# 3_TopLevel.net
KiCad netlist of a schematic drawn in Altium Designer
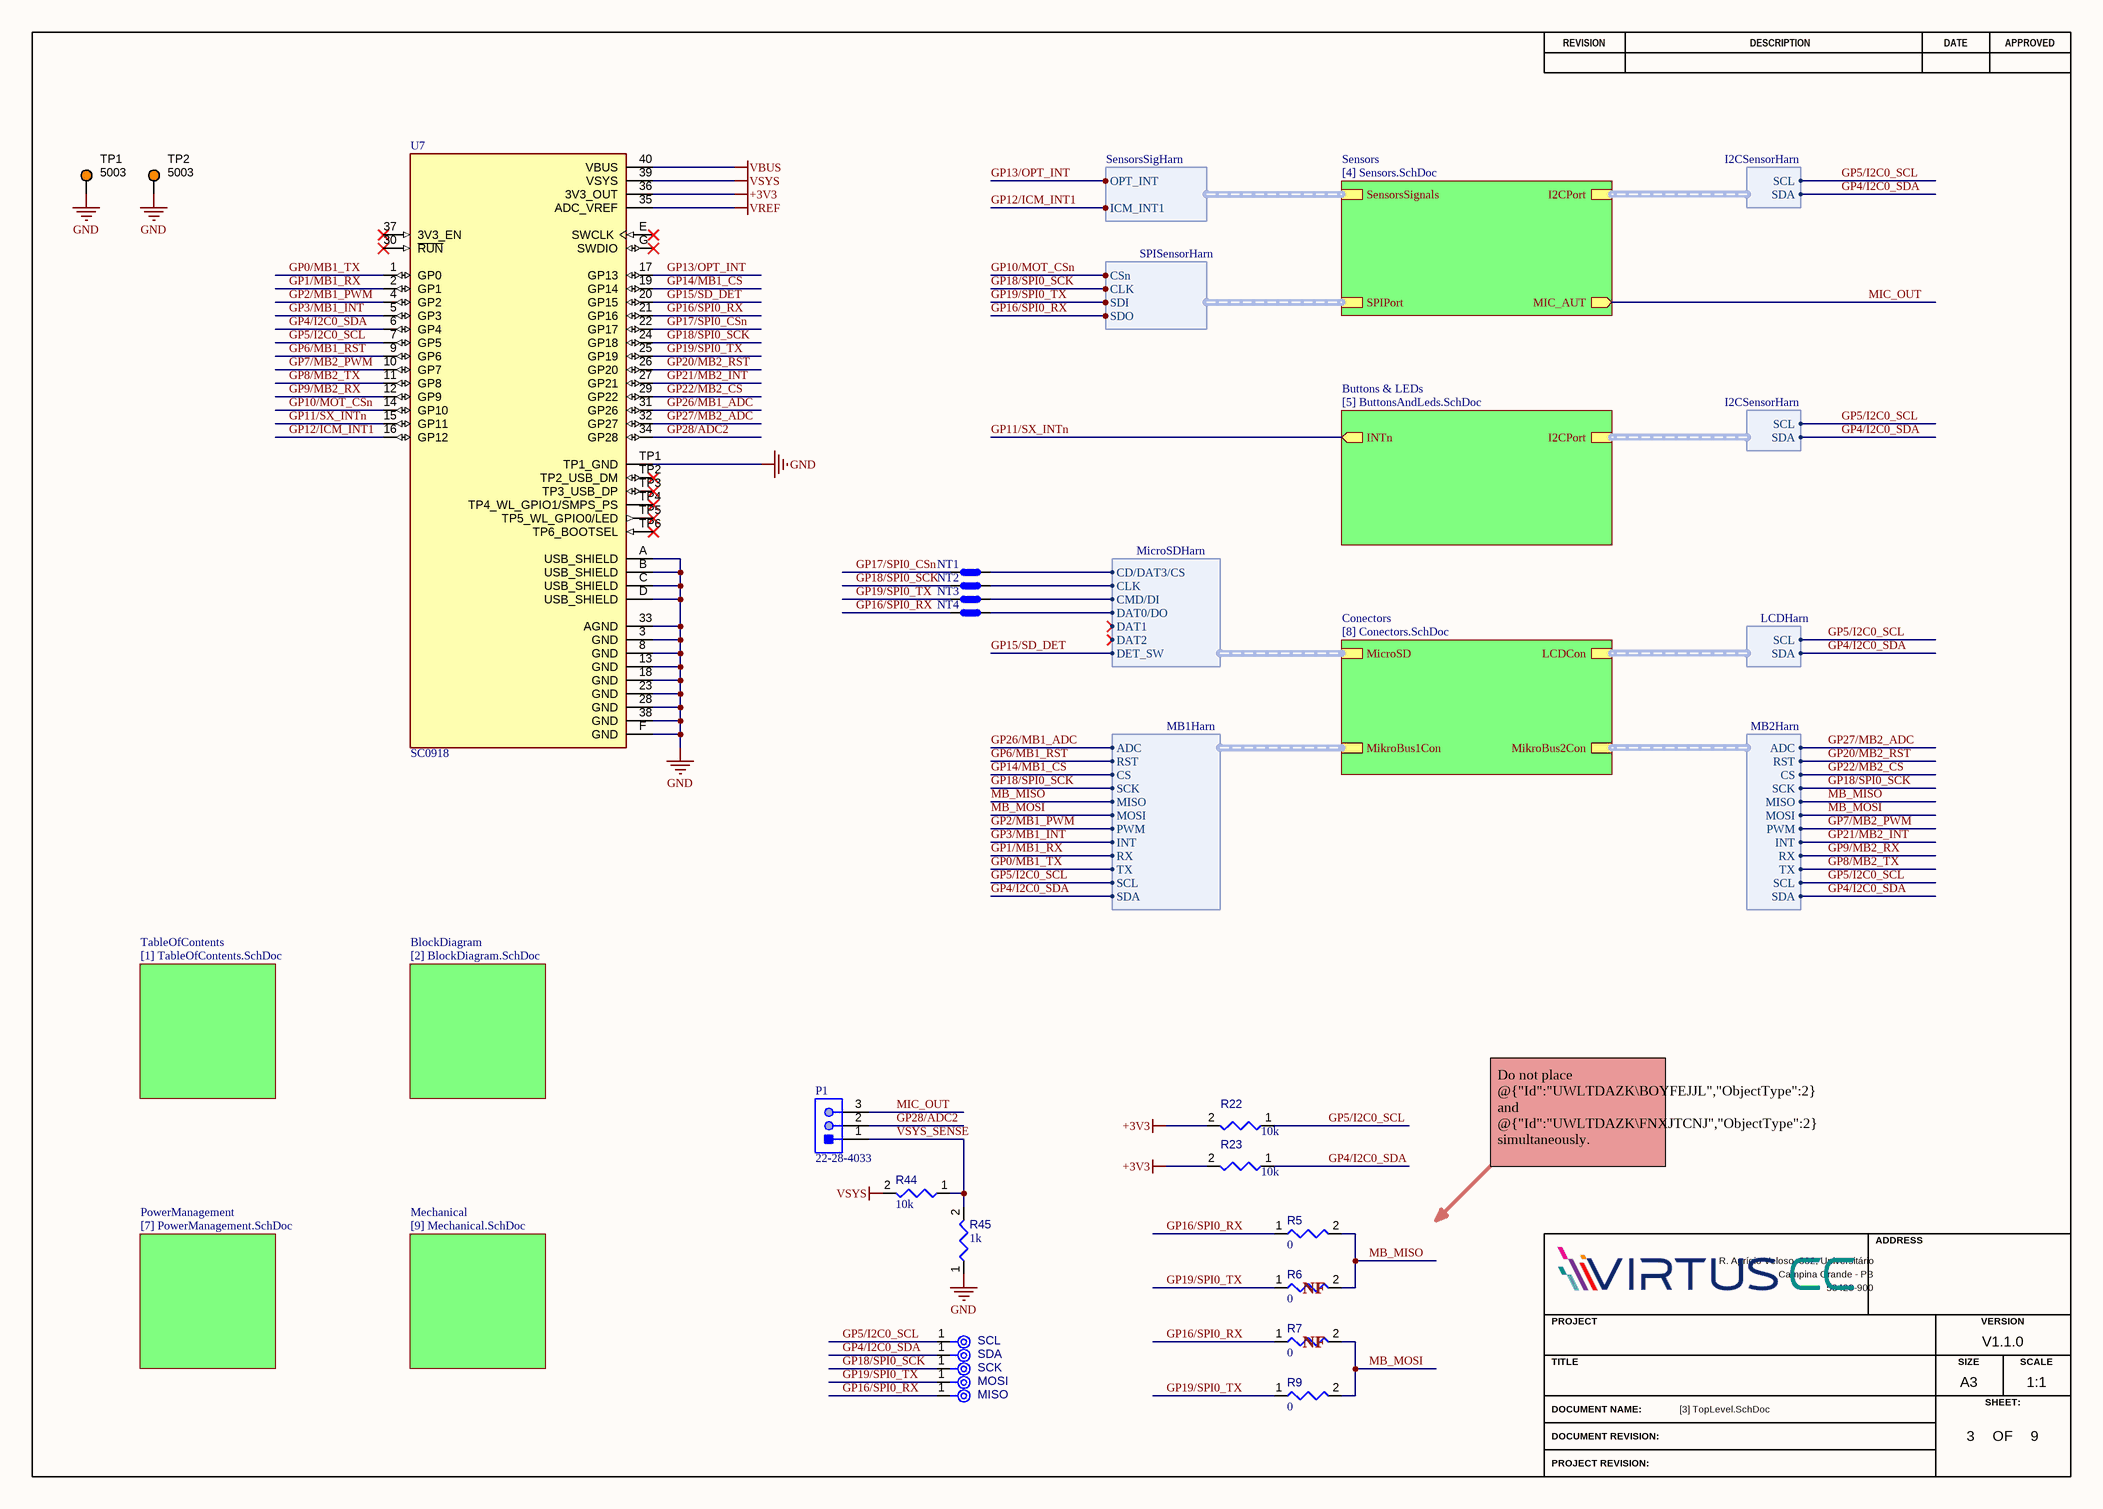
[diagram p0: [3] TopLevel.SchDoc]

(export (version "E")
  (design (tool "Eeschema 10.0.6"))
  (components
    (comp (ref "MISO")
      (value "TPAD6R")
      (footprint "TP06R")
      (description "0.6mm round")
      (libsource (lib "UFCG - Universidade Federal de Campina Grande") (part "CMP-001-0001-4"))
    )
    (comp (ref "MOSI")
      (value "TPAD6R")
      (footprint "TP06R")
      (description "0.6mm round")
      (libsource (lib "UFCG - Universidade Federal de Campina Grande") (part "CMP-001-0001-4"))
    )
    (comp (ref "NT1")
      (value "Net Tie")
      (footprint "New footprint 1")
      (description "Net Tie 0.3mm")
      (libsource (lib "UFCG - Universidade Federal de Campina Grande") (part "NetTie"))
    )
    (comp (ref "NT2")
      (value "Net Tie")
      (footprint "New footprint 1")
      (description "Net Tie 0.3mm")
      (libsource (lib "UFCG - Universidade Federal de Campina Grande") (part "NetTie"))
    )
    (comp (ref "NT3")
      (value "Net Tie")
      (footprint "New footprint 1")
      (description "Net Tie 0.3mm")
      (libsource (lib "UFCG - Universidade Federal de Campina Grande") (part "NetTie"))
    )
    (comp (ref "NT4")
      (value "Net Tie")
      (footprint "New footprint 1")
      (description "Net Tie 0.3mm")
      (libsource (lib "UFCG - Universidade Federal de Campina Grande") (part "NetTie"))
    )
    (comp (ref "P1")
      (value "22-28-4033")
      (footprint "MOLX-22-28-4033_V")
      (description "KK 254 Breakaway Header Vertical 3 Circuits 0.38um Gold Selective Plating Mating Pin 6.09mm")
      (libsource (lib "UFCG - Universidade Federal de Campina Grande") (part "CN-1P-M-R3"))
    )
    (comp (ref "R5")
      (value "0")
      (footprint "RESC0603(1608)_L")
      (description "Chip Resistor, 0 Ohm, 0.1 W, -55 to 155 degC, 0603 (1608 Metric)")
      (fields (field (name "TOLERANCE") "5%") (field (name "POWER") "100mW"))
      (libsource (lib "UFCG - Universidade Federal de Campina Grande") (part "RES-2"))
    )
    (comp (ref "R6")
      (value "0")
      (footprint "RESC0603(1608)_L")
      (description "Chip Resistor, 0 Ohm, 0.1 W, -55 to 155 degC, 0603 (1608 Metric)")
      (fields (field (name "TOLERANCE") "5%") (field (name "POWER") "100mW"))
      (libsource (lib "UFCG - Universidade Federal de Campina Grande") (part "RES-2"))
    )
    (comp (ref "R7")
      (value "0")
      (footprint "RESC0603(1608)_L")
      (description "Chip Resistor, 0 Ohm, 0.1 W, -55 to 155 degC, 0603 (1608 Metric)")
      (fields (field (name "TOLERANCE") "5%") (field (name "POWER") "100mW"))
      (libsource (lib "UFCG - Universidade Federal de Campina Grande") (part "RES-2"))
    )
    (comp (ref "R9")
      (value "0")
      (footprint "RESC0603(1608)_L")
      (description "Chip Resistor, 0 Ohm, 0.1 W, -55 to 155 degC, 0603 (1608 Metric)")
      (fields (field (name "TOLERANCE") "5%") (field (name "POWER") "100mW"))
      (libsource (lib "UFCG - Universidade Federal de Campina Grande") (part "RES-2"))
    )
    (comp (ref "R22")
      (value "10k")
      (footprint "RESC0603(1608)_L")
      (description "Chip Resistor, 10 KOhm, +/- 1%, 01 W, -55 to 155 degC, 0603 (1608 Metric)")
      (fields (field (name "POWER") "100mW") (field (name "TOLERANCE") "1%"))
      (libsource (lib "UFCG - Universidade Federal de Campina Grande") (part "RES-2"))
    )
    (comp (ref "R23")
      (value "10k")
      (footprint "RESC0603(1608)_L")
      (description "Chip Resistor, 10 KOhm, +/- 1%, 01 W, -55 to 155 degC, 0603 (1608 Metric)")
      (fields (field (name "POWER") "100mW") (field (name "TOLERANCE") "1%"))
      (libsource (lib "UFCG - Universidade Federal de Campina Grande") (part "RES-2"))
    )
    (comp (ref "R44")
      (value "10k")
      (footprint "RESC0603(1608)_L")
      (description "Chip Resistor, 10 KOhm, +/- 1%, 01 W, -55 to 155 degC, 0603 (1608 Metric)")
      (fields (field (name "POWER") "100mW") (field (name "TOLERANCE") "1%"))
      (libsource (lib "UFCG - Universidade Federal de Campina Grande") (part "RES-2"))
    )
    (comp (ref "R45")
      (value "1k")
      (footprint "RESC0603(1608)_L")
      (description "Chip Resistor, 1 KOhm, +/-1%, 0.1 W, -55 to 155 degC, 0603 (1608 Metric)")
      (fields (field (name "POWER") "100mW") (field (name "TOLERANCE") "1%"))
      (libsource (lib "UFCG - Universidade Federal de Campina Grande") (part "RES-2"))
    )
    (comp (ref "SCK")
      (value "TPAD6R")
      (footprint "TP06R")
      (description "0.6mm round")
      (libsource (lib "UFCG - Universidade Federal de Campina Grande") (part "CMP-001-0001-4"))
    )
    (comp (ref "SCL")
      (value "TPAD6R")
      (footprint "TP06R")
      (description "0.6mm round")
      (libsource (lib "UFCG - Universidade Federal de Campina Grande") (part "CMP-001-0001-4"))
    )
    (comp (ref "SDA")
      (value "TPAD6R")
      (footprint "TP06R")
      (description "0.6mm round")
      (libsource (lib "UFCG - Universidade Federal de Campina Grande") (part "CMP-001-0001-4"))
    )
    (comp (ref "TP1")
      (value "5003")
      (footprint "KSTN-5003")
      (description "Test Point, Orange, Height 4.6 mm, Tail Length 3 mm, 1-Pin THD, RoHS")
      (fields (field (name "MANUFACTURER") "Keystone"))
      (libsource (lib "UFCG - Universidade Federal de Campina Grande") (part "TESTPOINT_ORANGE"))
    )
    (comp (ref "TP2")
      (value "5003")
      (footprint "KSTN-5003")
      (description "Test Point, Orange, Height 4.6 mm, Tail Length 3 mm, 1-Pin THD, RoHS")
      (fields (field (name "MANUFACTURER") "Keystone"))
      (libsource (lib "UFCG - Universidade Federal de Campina Grande") (part "TESTPOINT_ORANGE"))
    )
    (comp (ref "U7")
      (value "SC0918")
      (footprint "MODULE_SC0918")
      (description "Raspberry Pi Pico W RP2040")
      (fields (field (name "MF") "Raspberry Pi"))
      (libsource (lib "UFCG - Universidade Federal de Campina Grande") (part "SC0918"))
    )
  )
  (nets
    (net (code "8") (name "+3V3") (class "Default")
      (node (ref "R22") (pin "2") (pinfunction "2_2") (pintype "passive"))
      (node (ref "R23") (pin "2") (pinfunction "2_2") (pintype "passive"))
      (node (ref "U7") (pin "36") (pinfunction "3V3_OUT_36") (pintype "power_in"))
    )
    (net (code "9") (name "/CD{slash}DAT3{slash}CS") (class "Default")
      (node (ref "NT1") (pin "2") (pintype "passive"))
    )
    (net (code "10") (name "/CMD{slash}DI") (class "Default")
      (node (ref "NT3") (pin "2") (pintype "passive"))
    )
    (net (code "11") (name "/DAT0{slash}DO") (class "Default")
      (node (ref "NT4") (pin "2") (pintype "passive"))
    )
    (net (code "12") (name "/GP0{slash}MB1_TX") (class "Default")
      (node (ref "U7") (pin "1") (pinfunction "GP0_1") (pintype "bidirectional"))
    )
    (net (code "13") (name "/GP1{slash}MB1_RX") (class "Default")
      (node (ref "U7") (pin "2") (pinfunction "GP1_2") (pintype "bidirectional"))
    )
    (net (code "14") (name "/GP2{slash}MB1_PWM") (class "Default")
      (node (ref "U7") (pin "4") (pinfunction "GP2_4") (pintype "bidirectional"))
    )
    (net (code "15") (name "/GP3{slash}MB1_INT") (class "Default")
      (node (ref "U7") (pin "5") (pinfunction "GP3_5") (pintype "bidirectional"))
    )
    (net (code "16") (name "/GP4{slash}I2C0_SDA") (class "Default")
      (node (ref "R23") (pin "1") (pinfunction "1_1") (pintype "passive"))
      (node (ref "SDA") (pin "1") (pinfunction "TP_1") (pintype "passive"))
      (node (ref "U7") (pin "6") (pinfunction "GP4_6") (pintype "bidirectional"))
    )
    (net (code "17") (name "/GP5{slash}I2C0_SCL") (class "Default")
      (node (ref "R22") (pin "1") (pinfunction "1_1") (pintype "passive"))
      (node (ref "SCL") (pin "1") (pinfunction "TP_1") (pintype "passive"))
      (node (ref "U7") (pin "7") (pinfunction "GP5_7") (pintype "bidirectional"))
    )
    (net (code "18") (name "/GP6{slash}MB1_RST") (class "Default")
      (node (ref "U7") (pin "9") (pinfunction "GP6_9") (pintype "bidirectional"))
    )
    (net (code "19") (name "/GP7{slash}MB2_PWM") (class "Default")
      (node (ref "U7") (pin "10") (pinfunction "GP7_10") (pintype "bidirectional"))
    )
    (net (code "20") (name "/GP8{slash}MB2_TX") (class "Default")
      (node (ref "U7") (pin "11") (pinfunction "GP8_11") (pintype "bidirectional"))
    )
    (net (code "21") (name "/GP9{slash}MB2_RX") (class "Default")
      (node (ref "U7") (pin "12") (pinfunction "GP9_12") (pintype "bidirectional"))
    )
    (net (code "22") (name "/GP10{slash}MOT_CSn") (class "Default")
      (node (ref "U7") (pin "14") (pinfunction "GP10_14") (pintype "bidirectional"))
    )
    (net (code "23") (name "/GP11{slash}SX_INTn") (class "Default")
      (node (ref "U7") (pin "15") (pinfunction "GP11_15") (pintype "bidirectional"))
    )
    (net (code "24") (name "/GP12{slash}ICM_INT1") (class "Default")
      (node (ref "U7") (pin "16") (pinfunction "GP12_16") (pintype "bidirectional"))
    )
    (net (code "25") (name "/GP13{slash}OPT_INT") (class "Default")
      (node (ref "U7") (pin "17") (pinfunction "GP13_17") (pintype "bidirectional"))
    )
    (net (code "26") (name "/GP14{slash}MB1_CS") (class "Default")
      (node (ref "U7") (pin "19") (pinfunction "GP14_19") (pintype "bidirectional"))
    )
    (net (code "27") (name "/GP15{slash}SD_DET") (class "Default")
      (node (ref "U7") (pin "20") (pinfunction "GP15_20") (pintype "bidirectional"))
    )
    (net (code "28") (name "/GP16{slash}SPI0_RX") (class "Default")
      (node (ref "MISO") (pin "1") (pinfunction "TP_1") (pintype "passive"))
      (node (ref "NT4") (pin "1") (pintype "passive"))
      (node (ref "R5") (pin "1") (pinfunction "1_1") (pintype "passive"))
      (node (ref "R7") (pin "1") (pinfunction "1_1") (pintype "passive"))
      (node (ref "U7") (pin "21") (pinfunction "GP16_21") (pintype "bidirectional"))
    )
    (net (code "29") (name "/GP17{slash}SPI0_CSn") (class "Default")
      (node (ref "NT1") (pin "1") (pintype "passive"))
      (node (ref "U7") (pin "22") (pinfunction "GP17_22") (pintype "bidirectional"))
    )
    (net (code "30") (name "/GP18{slash}SPI0_SCK") (class "Default")
      (node (ref "NT2") (pin "1") (pintype "passive"))
      (node (ref "SCK") (pin "1") (pinfunction "TP_1") (pintype "passive"))
      (node (ref "U7") (pin "24") (pinfunction "GP18_24") (pintype "bidirectional"))
    )
    (net (code "31") (name "/GP19{slash}SPI0_TX") (class "Default")
      (node (ref "MOSI") (pin "1") (pinfunction "TP_1") (pintype "passive"))
      (node (ref "NT3") (pin "1") (pintype "passive"))
      (node (ref "R6") (pin "1") (pinfunction "1_1") (pintype "passive"))
      (node (ref "R9") (pin "1") (pinfunction "1_1") (pintype "passive"))
      (node (ref "U7") (pin "25") (pinfunction "GP19_25") (pintype "bidirectional"))
    )
    (net (code "32") (name "/GP20{slash}MB2_RST") (class "Default")
      (node (ref "U7") (pin "26") (pinfunction "GP20_26") (pintype "bidirectional"))
    )
    (net (code "33") (name "/GP21{slash}MB2_INT") (class "Default")
      (node (ref "U7") (pin "27") (pinfunction "GP21_27") (pintype "bidirectional"))
    )
    (net (code "34") (name "/GP22{slash}MB2_CS") (class "Default")
      (node (ref "U7") (pin "29") (pinfunction "GP22_29") (pintype "bidirectional"))
    )
    (net (code "35") (name "/GP26{slash}MB1_ADC") (class "Default")
      (node (ref "U7") (pin "31") (pinfunction "GP26_31") (pintype "bidirectional"))
    )
    (net (code "36") (name "/GP27{slash}MB2_ADC") (class "Default")
      (node (ref "U7") (pin "32") (pinfunction "GP27_32") (pintype "bidirectional"))
    )
    (net (code "37") (name "/GP28{slash}ADC2") (class "Default")
      (node (ref "P1") (pin "2") (pinfunction "2_2") (pintype "passive"))
      (node (ref "U7") (pin "34") (pinfunction "GP28_34") (pintype "bidirectional"))
    )
    (net (code "38") (name "/MB_MISO") (class "Default")
      (node (ref "R5") (pin "2") (pinfunction "2_2") (pintype "passive"))
      (node (ref "R6") (pin "2") (pinfunction "2_2") (pintype "passive"))
    )
    (net (code "39") (name "/MB_MOSI") (class "Default")
      (node (ref "R7") (pin "2") (pinfunction "2_2") (pintype "passive"))
      (node (ref "R9") (pin "2") (pinfunction "2_2") (pintype "passive"))
    )
    (net (code "40") (name "/MIC_OUT") (class "Default")
      (node (ref "P1") (pin "3") (pinfunction "3_3") (pintype "passive"))
    )
    (net (code "41") (name "/VSYS_SENSE") (class "Default")
      (node (ref "P1") (pin "1") (pinfunction "1_1") (pintype "passive"))
      (node (ref "R44") (pin "1") (pinfunction "1_1") (pintype "passive"))
      (node (ref "R45") (pin "2") (pinfunction "2_2") (pintype "passive"))
    )
    (net (code "49") (name "GND") (class "Default")
      (node (ref "R45") (pin "1") (pinfunction "1_1") (pintype "passive"))
      (node (ref "TP1") (pin "1") (pinfunction "1_1") (pintype "passive"))
      (node (ref "TP2") (pin "1") (pinfunction "1_1") (pintype "passive"))
      (node (ref "U7") (pin "13") (pinfunction "GND_13") (pintype "power_in"))
      (node (ref "U7") (pin "18") (pinfunction "GND_18") (pintype "power_in"))
      (node (ref "U7") (pin "23") (pinfunction "GND_23") (pintype "power_in"))
      (node (ref "U7") (pin "28") (pinfunction "GND_28") (pintype "power_in"))
      (node (ref "U7") (pin "3") (pinfunction "GND_3") (pintype "power_in"))
      (node (ref "U7") (pin "33") (pinfunction "AGND_33") (pintype "power_in"))
      (node (ref "U7") (pin "38") (pinfunction "GND_38") (pintype "power_in"))
      (node (ref "U7") (pin "8") (pinfunction "GND_8") (pintype "power_in"))
      (node (ref "U7") (pin "A") (pinfunction "USB_SHIELD_A") (pintype "power_in"))
      (node (ref "U7") (pin "B") (pinfunction "USB_SHIELD_B") (pintype "power_in"))
      (node (ref "U7") (pin "C") (pinfunction "USB_SHIELD_C") (pintype "power_in"))
      (node (ref "U7") (pin "D") (pinfunction "USB_SHIELD_D") (pintype "power_in"))
      (node (ref "U7") (pin "F") (pinfunction "GND_F") (pintype "power_in"))
      (node (ref "U7") (pin "TP1") (pinfunction "TP1_GND_TP1") (pintype "power_in"))
    )
    (net (code "50") (name "VBUS") (class "Default")
      (node (ref "U7") (pin "40") (pinfunction "VBUS_40") (pintype "power_in"))
    )
    (net (code "51") (name "VREF") (class "Default")
      (node (ref "U7") (pin "35") (pinfunction "ADC_VREF_35") (pintype "power_in"))
    )
    (net (code "52") (name "VSYS") (class "Default")
      (node (ref "R44") (pin "2") (pinfunction "2_2") (pintype "passive"))
      (node (ref "U7") (pin "39") (pinfunction "VSYS_39") (pintype "power_in"))
    )
    (net (code "53") (name "unconnected-(NT2-Pad2)") (class "Default")
      (node (ref "NT2") (pin "2") (pintype "passive"))
    )
    (net (code "54") (name "unconnected-(U7-3V3_EN-Pad37)") (class "Default")
      (node (ref "U7") (pin "37") (pinfunction "3V3_EN_37") (pintype "input+no_connect"))
    )
    (net (code "55") (name "unconnected-(U7-SWCLK-PadE)") (class "Default")
      (node (ref "U7") (pin "E") (pinfunction "SWCLK_E") (pintype "input+no_connect"))
    )
    (net (code "56") (name "unconnected-(U7-SWDIO-PadG)") (class "Default")
      (node (ref "U7") (pin "G") (pinfunction "SWDIO_G") (pintype "bidirectional+no_connect"))
    )
    (net (code "57") (name "unconnected-(U7-TP2_USB_DM-PadTP2)") (class "Default")
      (node (ref "U7") (pin "TP2") (pinfunction "TP2_USB_DM_TP2") (pintype "bidirectional+no_connect"))
    )
    (net (code "58") (name "unconnected-(U7-TP3_USB_DP-PadTP3)") (class "Default")
      (node (ref "U7") (pin "TP3") (pinfunction "TP3_USB_DP_TP3") (pintype "bidirectional+no_connect"))
    )
    (net (code "59") (name "unconnected-(U7-TP4_WL_GPIO1{slash}SMPS_PS-PadTP4)") (class "Default")
      (node (ref "U7") (pin "TP4") (pinfunction "TP4_WL_GPIO1/SMPS_PS_TP4") (pintype "passive+no_connect"))
    )
    (net (code "60") (name "unconnected-(U7-TP5_WL_GPIO0{slash}LED-PadTP5)") (class "Default")
      (node (ref "U7") (pin "TP5") (pinfunction "TP5_WL_GPIO0/LED_TP5") (pintype "output+no_connect"))
    )
    (net (code "61") (name "unconnected-(U7-TP6_BOOTSEL-PadTP6)") (class "Default")
      (node (ref "U7") (pin "TP6") (pinfunction "TP6_BOOTSEL_TP6") (pintype "input+no_connect"))
    )
    (net (code "62") (name "unconnected-(U7-~{RUN}-Pad30)") (class "Default")
      (node (ref "U7") (pin "30") (pinfunction "~{RUN}_30") (pintype "input+no_connect"))
    )
  )
)
